# LCD.net
KiCad netlist of a schematic drawn in Altium Designer
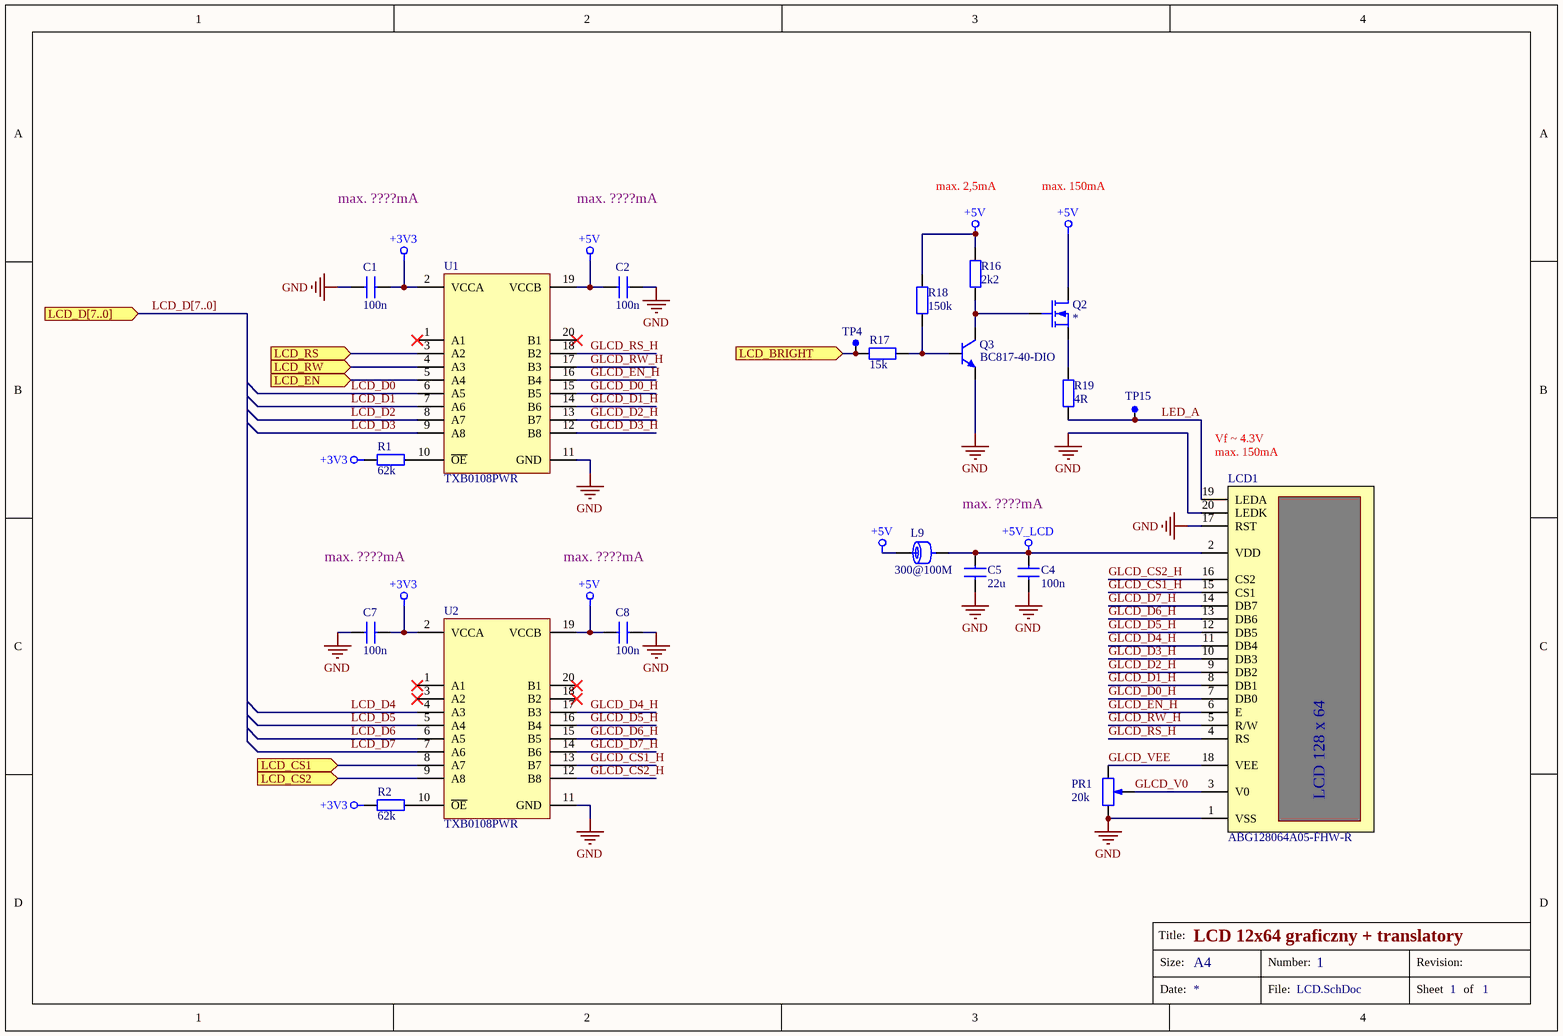
[diagram p0: LCD.SchDoc]

(export (version "E")
  (design (tool "Eeschema 10.0.6"))
  (components
    (comp (ref "C1")
      (value "100n")
      (footprint "C_0805")
      (description "Capacitor")
      (libsource (lib "passive") (part "Capacitor"))
    )
    (comp (ref "C2")
      (value "100n")
      (footprint "C_0805")
      (description "Capacitor")
      (libsource (lib "passive") (part "Capacitor"))
    )
    (comp (ref "C4")
      (value "100n")
      (footprint "C_0805")
      (description "Capacitor")
      (libsource (lib "passive") (part "Capacitor"))
    )
    (comp (ref "C5")
      (value "22u")
      (footprint "C_0805")
      (description "Capacitor")
      (libsource (lib "passive") (part "Capacitor"))
    )
    (comp (ref "C7")
      (value "100n")
      (footprint "C_0805")
      (description "Capacitor")
      (libsource (lib "passive") (part "Capacitor"))
    )
    (comp (ref "C8")
      (value "100n")
      (footprint "C_0805")
      (description "Capacitor")
      (libsource (lib "passive") (part "Capacitor"))
    )
    (comp (ref "L9")
      (value "300@100M")
      (footprint "L_0805")
      (description "Ferrite Bead")
      (fields (field (name "Comment") "742792031"))
      (libsource (lib "passive") (part "FB"))
    )
    (comp (ref "LCD1")
      (value "ABG128064A05-FHW-R")
      (footprint "GLCD")
      (description "Graphic LCD 128x64")
      (libsource (lib "digital") (part "LCD 128x64"))
    )
    (comp (ref "PR1")
      (value "T67W-20K")
      (footprint "1804 potentiometer")
      (description "3 pin Potentiometer")
      (fields (field (name "ALTIUM_UNNAMED_1") "20k"))
      (libsource (lib "passive") (part "Potentiometer"))
    )
    (comp (ref "Q2")
      (value "MOSFET-N")
      (footprint "SOT-23")
      (description "N-Channel MOSFET")
      (fields (field (name "ALTIUM_VALUE") "*"))
      (libsource (lib "passive") (part "MOSFET-N"))
    )
    (comp (ref "Q3")
      (value "BC817-40-DIO")
      (footprint "SOT-23")
      (description "NPN Bipolar Transistor")
      (libsource (lib "boxer_pas") (part "NPN"))
    )
    (comp (ref "R1")
      (value "62k")
      (footprint "R_0805")
      (description "Resistor")
      (libsource (lib "passive") (part "Resistor"))
    )
    (comp (ref "R2")
      (value "62k")
      (footprint "R_0805")
      (description "Resistor")
      (libsource (lib "passive") (part "Resistor"))
    )
    (comp (ref "R16")
      (value "2k2")
      (footprint "R_0805")
      (description "Resistor")
      (libsource (lib "") (part "Resistor_2"))
    )
    (comp (ref "R17")
      (value "15k")
      (footprint "R_0805")
      (description "Resistor")
      (libsource (lib "boxer_pas") (part "Resistor"))
    )
    (comp (ref "R18")
      (value "150k")
      (footprint "R_0805")
      (description "Resistor")
      (libsource (lib "") (part "Resistor_2"))
    )
    (comp (ref "R19")
      (value "4R")
      (footprint "R_1206")
      (description "Resistor")
      (libsource (lib "") (part "Resistor_1"))
    )
    (comp (ref "TP4")
      (value "TEST PAD")
      (footprint "PIN")
      (description "PAD 1.5mm")
      (libsource (lib "boxer_mechanical") (part "TEST_PAD"))
    )
    (comp (ref "TP15")
      (value "TEST PAD")
      (footprint "PIN")
      (description "PAD 1.5mm")
      (libsource (lib "boxer_mechanical") (part "TEST_PAD"))
    )
    (comp (ref "U1") (value "TXB0108PWR") (footprint "TSSOP20") (libsource (lib "digital") (part "TXB0108")))
    (comp (ref "U2") (value "TXB0108PWR") (footprint "TSSOP20") (libsource (lib "digital") (part "TXB0108")))
  )
  (nets
    (net (code "1") (name "+3V3") (class "Default")
      (node (ref "C1") (pin "1") (pinfunction "1_1") (pintype "passive"))
      (node (ref "C7") (pin "1") (pinfunction "1_1") (pintype "passive"))
      (node (ref "R1") (pin "1") (pinfunction "1_1") (pintype "passive"))
      (node (ref "R2") (pin "1") (pinfunction "1_1") (pintype "passive"))
      (node (ref "U1") (pin "2") (pinfunction "VCCA_2") (pintype "passive"))
      (node (ref "U2") (pin "2") (pinfunction "VCCA_2") (pintype "passive"))
    )
    (net (code "2") (name "+5V") (class "Default")
      (node (ref "C2") (pin "2") (pinfunction "2_2") (pintype "passive"))
      (node (ref "C8") (pin "2") (pinfunction "2_2") (pintype "passive"))
      (node (ref "L9") (pin "1") (pinfunction "1_1") (pintype "passive"))
      (node (ref "Q2") (pin "3") (pinfunction "D_3") (pintype "passive"))
      (node (ref "R16") (pin "2") (pinfunction "2_2") (pintype "passive"))
      (node (ref "R18") (pin "2") (pinfunction "2_2") (pintype "passive"))
      (node (ref "U1") (pin "19") (pinfunction "VCCB_19") (pintype "passive"))
      (node (ref "U2") (pin "19") (pinfunction "VCCB_19") (pintype "passive"))
    )
    (net (code "3") (name "+5V_LCD") (class "Default")
      (node (ref "C4") (pin "1") (pinfunction "1_1") (pintype "passive"))
      (node (ref "C5") (pin "1") (pinfunction "1_1") (pintype "passive"))
      (node (ref "L9") (pin "2") (pinfunction "2_2") (pintype "passive"))
      (node (ref "LCD1") (pin "2") (pinfunction "VDD_2") (pintype "passive"))
    )
    (net (code "4") (name "/GLCD_CS1_H") (class "Default")
      (node (ref "LCD1") (pin "15") (pinfunction "CS1_15") (pintype "passive"))
      (node (ref "U2") (pin "13") (pinfunction "B7_13") (pintype "passive"))
    )
    (net (code "5") (name "/GLCD_CS2_H") (class "Default")
      (node (ref "LCD1") (pin "16") (pinfunction "CS2_16") (pintype "passive"))
      (node (ref "U2") (pin "12") (pinfunction "B8_12") (pintype "passive"))
    )
    (net (code "6") (name "/GLCD_D0_H") (class "Default")
      (node (ref "LCD1") (pin "7") (pinfunction "DB0_7") (pintype "passive"))
      (node (ref "U1") (pin "15") (pinfunction "B5_15") (pintype "passive"))
    )
    (net (code "7") (name "/GLCD_D1_H") (class "Default")
      (node (ref "LCD1") (pin "8") (pinfunction "DB1_8") (pintype "passive"))
      (node (ref "U1") (pin "14") (pinfunction "B6_14") (pintype "passive"))
    )
    (net (code "8") (name "/GLCD_D2_H") (class "Default")
      (node (ref "LCD1") (pin "9") (pinfunction "DB2_9") (pintype "passive"))
      (node (ref "U1") (pin "13") (pinfunction "B7_13") (pintype "passive"))
    )
    (net (code "9") (name "/GLCD_D3_H") (class "Default")
      (node (ref "LCD1") (pin "10") (pinfunction "DB3_10") (pintype "passive"))
      (node (ref "U1") (pin "12") (pinfunction "B8_12") (pintype "passive"))
    )
    (net (code "10") (name "/GLCD_D4_H") (class "Default")
      (node (ref "LCD1") (pin "11") (pinfunction "DB4_11") (pintype "passive"))
      (node (ref "U2") (pin "17") (pinfunction "B3_17") (pintype "passive"))
    )
    (net (code "11") (name "/GLCD_D5_H") (class "Default")
      (node (ref "LCD1") (pin "12") (pinfunction "DB5_12") (pintype "passive"))
      (node (ref "U2") (pin "16") (pinfunction "B4_16") (pintype "passive"))
    )
    (net (code "12") (name "/GLCD_D6_H") (class "Default")
      (node (ref "LCD1") (pin "13") (pinfunction "DB6_13") (pintype "passive"))
      (node (ref "U2") (pin "15") (pinfunction "B5_15") (pintype "passive"))
    )
    (net (code "13") (name "/GLCD_D7_H") (class "Default")
      (node (ref "LCD1") (pin "14") (pinfunction "DB7_14") (pintype "passive"))
      (node (ref "U2") (pin "14") (pinfunction "B6_14") (pintype "passive"))
    )
    (net (code "14") (name "/GLCD_EN_H") (class "Default")
      (node (ref "LCD1") (pin "6") (pinfunction "E_6") (pintype "passive"))
      (node (ref "U1") (pin "16") (pinfunction "B4_16") (pintype "passive"))
    )
    (net (code "15") (name "/GLCD_RS_H") (class "Default")
      (node (ref "LCD1") (pin "4") (pinfunction "RS_4") (pintype "passive"))
      (node (ref "U1") (pin "18") (pinfunction "B2_18") (pintype "passive"))
    )
    (net (code "16") (name "/GLCD_RW_H") (class "Default")
      (node (ref "LCD1") (pin "5") (pinfunction "R/W_5") (pintype "passive"))
      (node (ref "U1") (pin "17") (pinfunction "B3_17") (pintype "passive"))
    )
    (net (code "17") (name "/GLCD_V0") (class "Default")
      (node (ref "LCD1") (pin "3") (pinfunction "V0_3") (pintype "passive"))
      (node (ref "PR1") (pin "2") (pinfunction "TAP_2") (pintype "passive"))
    )
    (net (code "18") (name "/GLCD_VEE") (class "Default")
      (node (ref "LCD1") (pin "18") (pinfunction "VEE_18") (pintype "passive"))
      (node (ref "PR1") (pin "3") (pinfunction "TOP_3") (pintype "passive"))
    )
    (net (code "19") (name "/LCD_BRIGHT") (class "Default")
      (node (ref "R17") (pin "1") (pinfunction "1_1") (pintype "passive"))
      (node (ref "TP4") (pin "1") (pinfunction "1_1") (pintype "passive"))
    )
    (net (code "20") (name "/LCD_CS1") (class "Default")
      (node (ref "U2") (pin "8") (pinfunction "A7_8") (pintype "passive"))
    )
    (net (code "21") (name "/LCD_CS2") (class "Default")
      (node (ref "U2") (pin "9") (pinfunction "A8_9") (pintype "passive"))
    )
    (net (code "22") (name "/LCD_D0") (class "Default")
      (node (ref "U1") (pin "6") (pinfunction "A5_6") (pintype "passive"))
    )
    (net (code "23") (name "/LCD_D1") (class "Default")
      (node (ref "U1") (pin "7") (pinfunction "A6_7") (pintype "passive"))
    )
    (net (code "24") (name "/LCD_D2") (class "Default")
      (node (ref "U1") (pin "8") (pinfunction "A7_8") (pintype "passive"))
    )
    (net (code "25") (name "/LCD_D3") (class "Default")
      (node (ref "U1") (pin "9") (pinfunction "A8_9") (pintype "passive"))
    )
    (net (code "26") (name "/LCD_D4") (class "Default")
      (node (ref "U2") (pin "4") (pinfunction "A3_4") (pintype "passive"))
    )
    (net (code "27") (name "/LCD_D5") (class "Default")
      (node (ref "U2") (pin "5") (pinfunction "A4_5") (pintype "passive"))
    )
    (net (code "28") (name "/LCD_D6") (class "Default")
      (node (ref "U2") (pin "6") (pinfunction "A5_6") (pintype "passive"))
    )
    (net (code "29") (name "/LCD_D7") (class "Default")
      (node (ref "U2") (pin "7") (pinfunction "A6_7") (pintype "passive"))
    )
    (net (code "31") (name "/LCD_EN") (class "Default")
      (node (ref "U1") (pin "5") (pinfunction "A4_5") (pintype "passive"))
    )
    (net (code "32") (name "/LCD_RS") (class "Default")
      (node (ref "U1") (pin "3") (pinfunction "A2_3") (pintype "passive"))
    )
    (net (code "33") (name "/LCD_RW") (class "Default")
      (node (ref "U1") (pin "4") (pinfunction "A3_4") (pintype "passive"))
    )
    (net (code "34") (name "/LED_A") (class "Default")
      (node (ref "LCD1") (pin "19") (pinfunction "LEDA_19") (pintype "passive"))
      (node (ref "R19") (pin "2") (pinfunction "2_2") (pintype "passive"))
      (node (ref "TP15") (pin "1") (pinfunction "1_1") (pintype "passive"))
    )
    (net (code "35") (name "GND") (class "Default")
      (node (ref "C1") (pin "2") (pinfunction "2_2") (pintype "passive"))
      (node (ref "C2") (pin "1") (pinfunction "1_1") (pintype "passive"))
      (node (ref "C4") (pin "2") (pinfunction "2_2") (pintype "passive"))
      (node (ref "C5") (pin "2") (pinfunction "2_2") (pintype "passive"))
      (node (ref "C7") (pin "2") (pinfunction "2_2") (pintype "passive"))
      (node (ref "C8") (pin "1") (pinfunction "1_1") (pintype "passive"))
      (node (ref "LCD1") (pin "1") (pinfunction "VSS_1") (pintype "passive"))
      (node (ref "LCD1") (pin "17") (pinfunction "RST_17") (pintype "passive"))
      (node (ref "LCD1") (pin "20") (pinfunction "LEDK_20") (pintype "passive"))
      (node (ref "PR1") (pin "1") (pinfunction "BOT_1") (pintype "passive"))
      (node (ref "Q3") (pin "2") (pinfunction "E_2") (pintype "passive"))
      (node (ref "U1") (pin "11") (pinfunction "GND_11") (pintype "passive"))
      (node (ref "U2") (pin "11") (pinfunction "GND_11") (pintype "passive"))
    )
    (net (code "36") (name "Net-(Q2-G)") (class "Default")
      (node (ref "Q2") (pin "1") (pinfunction "G_1") (pintype "passive"))
      (node (ref "Q3") (pin "3") (pinfunction "C_3") (pintype "passive"))
      (node (ref "R16") (pin "1") (pinfunction "1_1") (pintype "passive"))
    )
    (net (code "37") (name "Net-(Q2-S)") (class "Default")
      (node (ref "Q2") (pin "2") (pinfunction "S_2") (pintype "passive"))
      (node (ref "R19") (pin "1") (pinfunction "1_1") (pintype "passive"))
    )
    (net (code "38") (name "Net-(Q3-B)") (class "Default")
      (node (ref "Q3") (pin "1") (pinfunction "B_1") (pintype "passive"))
      (node (ref "R17") (pin "2") (pinfunction "2_2") (pintype "passive"))
      (node (ref "R18") (pin "1") (pinfunction "1_1") (pintype "passive"))
    )
    (net (code "39") (name "Net-(U1-~{OE})") (class "Default")
      (node (ref "R1") (pin "2") (pinfunction "2_2") (pintype "passive"))
      (node (ref "U1") (pin "10") (pinfunction "~{OE}_10") (pintype "passive"))
    )
    (net (code "40") (name "Net-(U2-~{OE})") (class "Default")
      (node (ref "R2") (pin "2") (pinfunction "2_2") (pintype "passive"))
      (node (ref "U2") (pin "10") (pinfunction "~{OE}_10") (pintype "passive"))
    )
    (net (code "41") (name "unconnected-(U1-A1-Pad1)") (class "Default")
      (node (ref "U1") (pin "1") (pinfunction "A1_1") (pintype "passive+no_connect"))
    )
    (net (code "42") (name "unconnected-(U1-B1-Pad20)") (class "Default")
      (node (ref "U1") (pin "20") (pinfunction "B1_20") (pintype "passive+no_connect"))
    )
    (net (code "43") (name "unconnected-(U2-A1-Pad1)") (class "Default")
      (node (ref "U2") (pin "1") (pinfunction "A1_1") (pintype "passive+no_connect"))
    )
    (net (code "44") (name "unconnected-(U2-A2-Pad3)") (class "Default")
      (node (ref "U2") (pin "3") (pinfunction "A2_3") (pintype "passive+no_connect"))
    )
    (net (code "45") (name "unconnected-(U2-B1-Pad20)") (class "Default")
      (node (ref "U2") (pin "20") (pinfunction "B1_20") (pintype "passive+no_connect"))
    )
    (net (code "46") (name "unconnected-(U2-B2-Pad18)") (class "Default")
      (node (ref "U2") (pin "18") (pinfunction "B2_18") (pintype "passive+no_connect"))
    )
  )
)
